# Main.net
KiCad netlist of a schematic drawn in Altium Designer
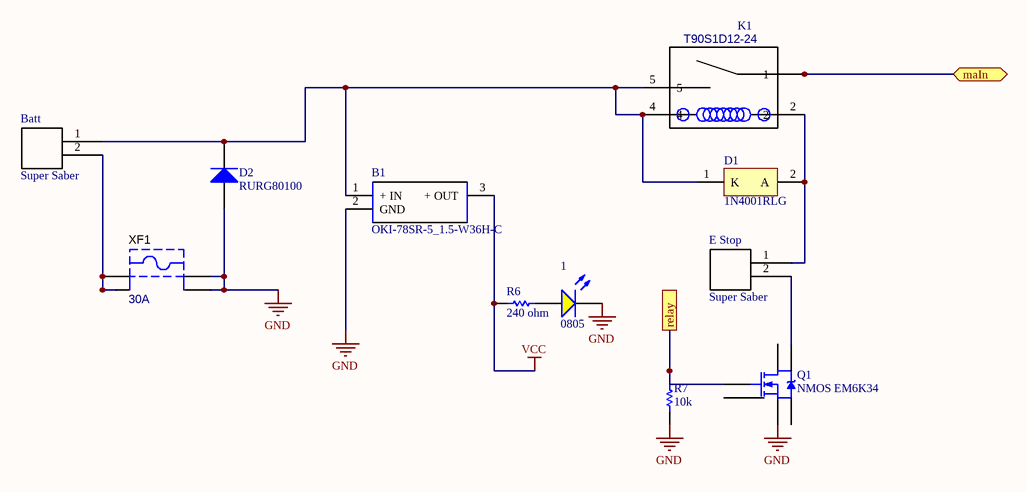
[diagram p0: Main.SchDoc]

(export (version "E")
  (design (tool "Eeschema 10.0.6"))
  (components
    (comp (ref "1")
      (value "0805")
      (footprint "LTST-C170YKT_V")
      (description "LED YELLOW CLEAR 0805 SMD")
      (fields (field (name "PARTNUMBER") "LTST-C170YKT"))
      (libsource (lib "Altium Content Vault") (part "LED_YELLOW_AC"))
    )
    (comp (ref "B1")
      (value "OKI-78SR-5_1.5-W36H-C")
      (footprint "OKI-78SR-HORIZONTAL")
      (description "Switching Regulator 7-36Vin 5Vo 1.5A Non-Isolated DC-DC Converter, 5V dc Output, 1.5A")
      (fields
        (field (name "MOUSER PART NUMBER") "580-OKI78SR51.5W36HC")
        (field (name "MANUFACTURER_PART_NUMBER") "OKI-78SR-5/1.5-W36H-C")
      )
      (libsource (lib "OKI-78SR-5_1.5-W36H-C") (part "OKI-78SR-5_1.5-W36H-C"))
    )
    (comp (ref "Batt")
      (value "Super Saber")
      (footprint "0431600102")
      (libsource (lib "Connector Schematic Symbols") (part "Super Saber"))
    )
    (comp (ref "D1")
      (value "1N4001RLG")
      (footprint "ONSC-AXIAL_LEAD-2-59-10_P")
      (description "Standard Recovery Rectifier, 2-Pin Axial_Lead, Pb-Free, Tape and Reel")
      (fields (field (name "MANUFACTURER") "On Semiconductor"))
      (libsource (lib "Altium Content Vault") (part "ONSC-D-K1A2-2_A"))
    )
    (comp (ref "D2")
      (value "RURG80100")
      (footprint "SMC")
      (description "Default Diode")
      (fields (field (name "PUBLISHER") "Altium Limited"))
      (libsource (lib "Miscellaneous Devices") (part "Diode"))
    )
    (comp (ref "E Stop")
      (value "Super Saber")
      (footprint "0431600102")
      (libsource (lib "Connector Schematic Symbols") (part "Super Saber"))
    )
    (comp (ref "K1")
      (value "T90S1D12-24")
      (footprint "TE_1-1393209-6")
      (fields (field (name "MF") "TE Connectivity"))
      (libsource (lib "1-1393209-6") (part "1-1393209-6"))
    )
    (comp (ref "Q1")
      (value "NMOS EM6K34")
      (footprint "*SOT50P160X55-6N")
      (description "N-Channel Power MOSFET")
      (fields (field (name "PUBLISHER") "Altium Limited"))
      (libsource (lib "Miscellaneous Devices") (part "NMOS-2"))
    )
    (comp (ref "R6")
      (value "240 ohm")
      (footprint "RESC0805(2012)_N")
      (description "160R 0.125W 1% 0805 (2012 Metric)  SMD")
      (fields (field (name "TOLERANCE") "1 %") (field (name "POWER") "0.125 W"))
      (libsource (lib "Altium Content Vault") (part "RES"))
    )
    (comp (ref "R7")
      (value "10k")
      (footprint "RESC0805(2012)_N")
      (description "160R 0.125W 1% 0805 (2012 Metric)  SMD")
      (fields (field (name "TOLERANCE") "1 %") (field (name "POWER") "0.125 W"))
      (libsource (lib "Altium Content Vault") (part "RES"))
    )
    (comp (ref "XF1")
      (value "30A")
      (footprint "KSTN-3568_V")
      (description "Fuse Holder, 30")
      (fields (field (name "MANUFACTURER") "Keystone"))
      (libsource (lib "Altium Content Vault") (part "FUSE_HOLDER-4"))
    )
  )
  (nets
    (net (code "1") (name "/maIn") (class "Default")
      (node (ref "K1") (pin "1") (pinfunction "1_1") (pintype "passive"))
      (node (ref "K1") (pin "3") (pinfunction "1_3") (pintype "passive"))
    )
    (net (code "2") (name "/relay") (class "Default")
      (node (ref "Q1") (pin "5") (pinfunction "G_5") (pintype "passive"))
      (node (ref "R7") (pin "2") (pinfunction "2_2") (pintype "passive"))
    )
    (net (code "3") (name "GND") (class "Default")
      (node (ref "1") (pin "C") (pinfunction "C_C") (pintype "passive"))
      (node (ref "B1") (pin "2") (pinfunction "GND_2") (pintype "passive"))
      (node (ref "D2") (pin "3") (pinfunction "A_3") (pintype "passive"))
      (node (ref "Q1") (pin "4") (pinfunction "S_4") (pintype "passive"))
      (node (ref "R7") (pin "1") (pinfunction "1_1") (pintype "passive"))
      (node (ref "XF1") (pin "3") (pinfunction "3_3") (pintype "passive"))
      (node (ref "XF1") (pin "4") (pinfunction "4_4") (pintype "passive"))
    )
    (net (code "4") (name "Net-(B1-+_IN)") (class "Default")
      (node (ref "B1") (pin "1") (pinfunction "+_IN_1") (pintype "passive"))
      (node (ref "Batt") (pin "1") (pintype "passive"))
      (node (ref "D1") (pin "1") (pinfunction "K_1") (pintype "passive"))
      (node (ref "D2") (pin "2") (pinfunction "K_2") (pintype "passive"))
      (node (ref "K1") (pin "4") (pinfunction "4_4") (pintype "passive"))
      (node (ref "K1") (pin "5") (pinfunction "5_5") (pintype "passive"))
    )
    (net (code "5") (name "Net-(Batt-Pad2)") (class "Default")
      (node (ref "Batt") (pin "2") (pintype "passive"))
      (node (ref "XF1") (pin "1") (pinfunction "1_1") (pintype "passive"))
      (node (ref "XF1") (pin "2") (pinfunction "2_2") (pintype "passive"))
    )
    (net (code "6") (name "Net-(D1-A)") (class "Default")
      (node (ref "D1") (pin "2") (pinfunction "A_2") (pintype "passive"))
      (node (ref "E Stop") (pin "1") (pintype "passive"))
      (node (ref "K1") (pin "2") (pinfunction "2_2") (pintype "passive"))
    )
    (net (code "7") (name "Net-(E Stop-Pad2)") (class "Default")
      (node (ref "E Stop") (pin "2") (pintype "passive"))
      (node (ref "Q1") (pin "3") (pinfunction "D_3") (pintype "passive"))
    )
    (net (code "8") (name "VCC") (class "Default")
      (node (ref "B1") (pin "3") (pinfunction "+_OUT_3") (pintype "passive"))
      (node (ref "R6") (pin "2") (pinfunction "2_2") (pintype "passive"))
    )
    (net (code "9") (name "unconnected-(1-PadA)") (class "Default")
      (node (ref "1") (pin "A") (pinfunction "A_A") (pintype "passive"))
    )
    (net (code "10") (name "unconnected-(Q1-D-Pad6)") (class "Default")
      (node (ref "Q1") (pin "6") (pinfunction "D_6") (pintype "passive"))
    )
    (net (code "11") (name "unconnected-(Q1-G-Pad2)") (class "Default")
      (node (ref "Q1") (pin "2") (pinfunction "G_2") (pintype "passive"))
    )
    (net (code "12") (name "unconnected-(Q1-S-Pad1)") (class "Default")
      (node (ref "Q1") (pin "1") (pinfunction "S_1") (pintype "passive"))
    )
    (net (code "13") (name "unconnected-(R6-Pad1)") (class "Default")
      (node (ref "R6") (pin "1") (pinfunction "1_1") (pintype "passive"))
    )
  )
)
